# EVGP_Estop_Daugherboard.net
KiCad netlist of a schematic drawn in EAGLE
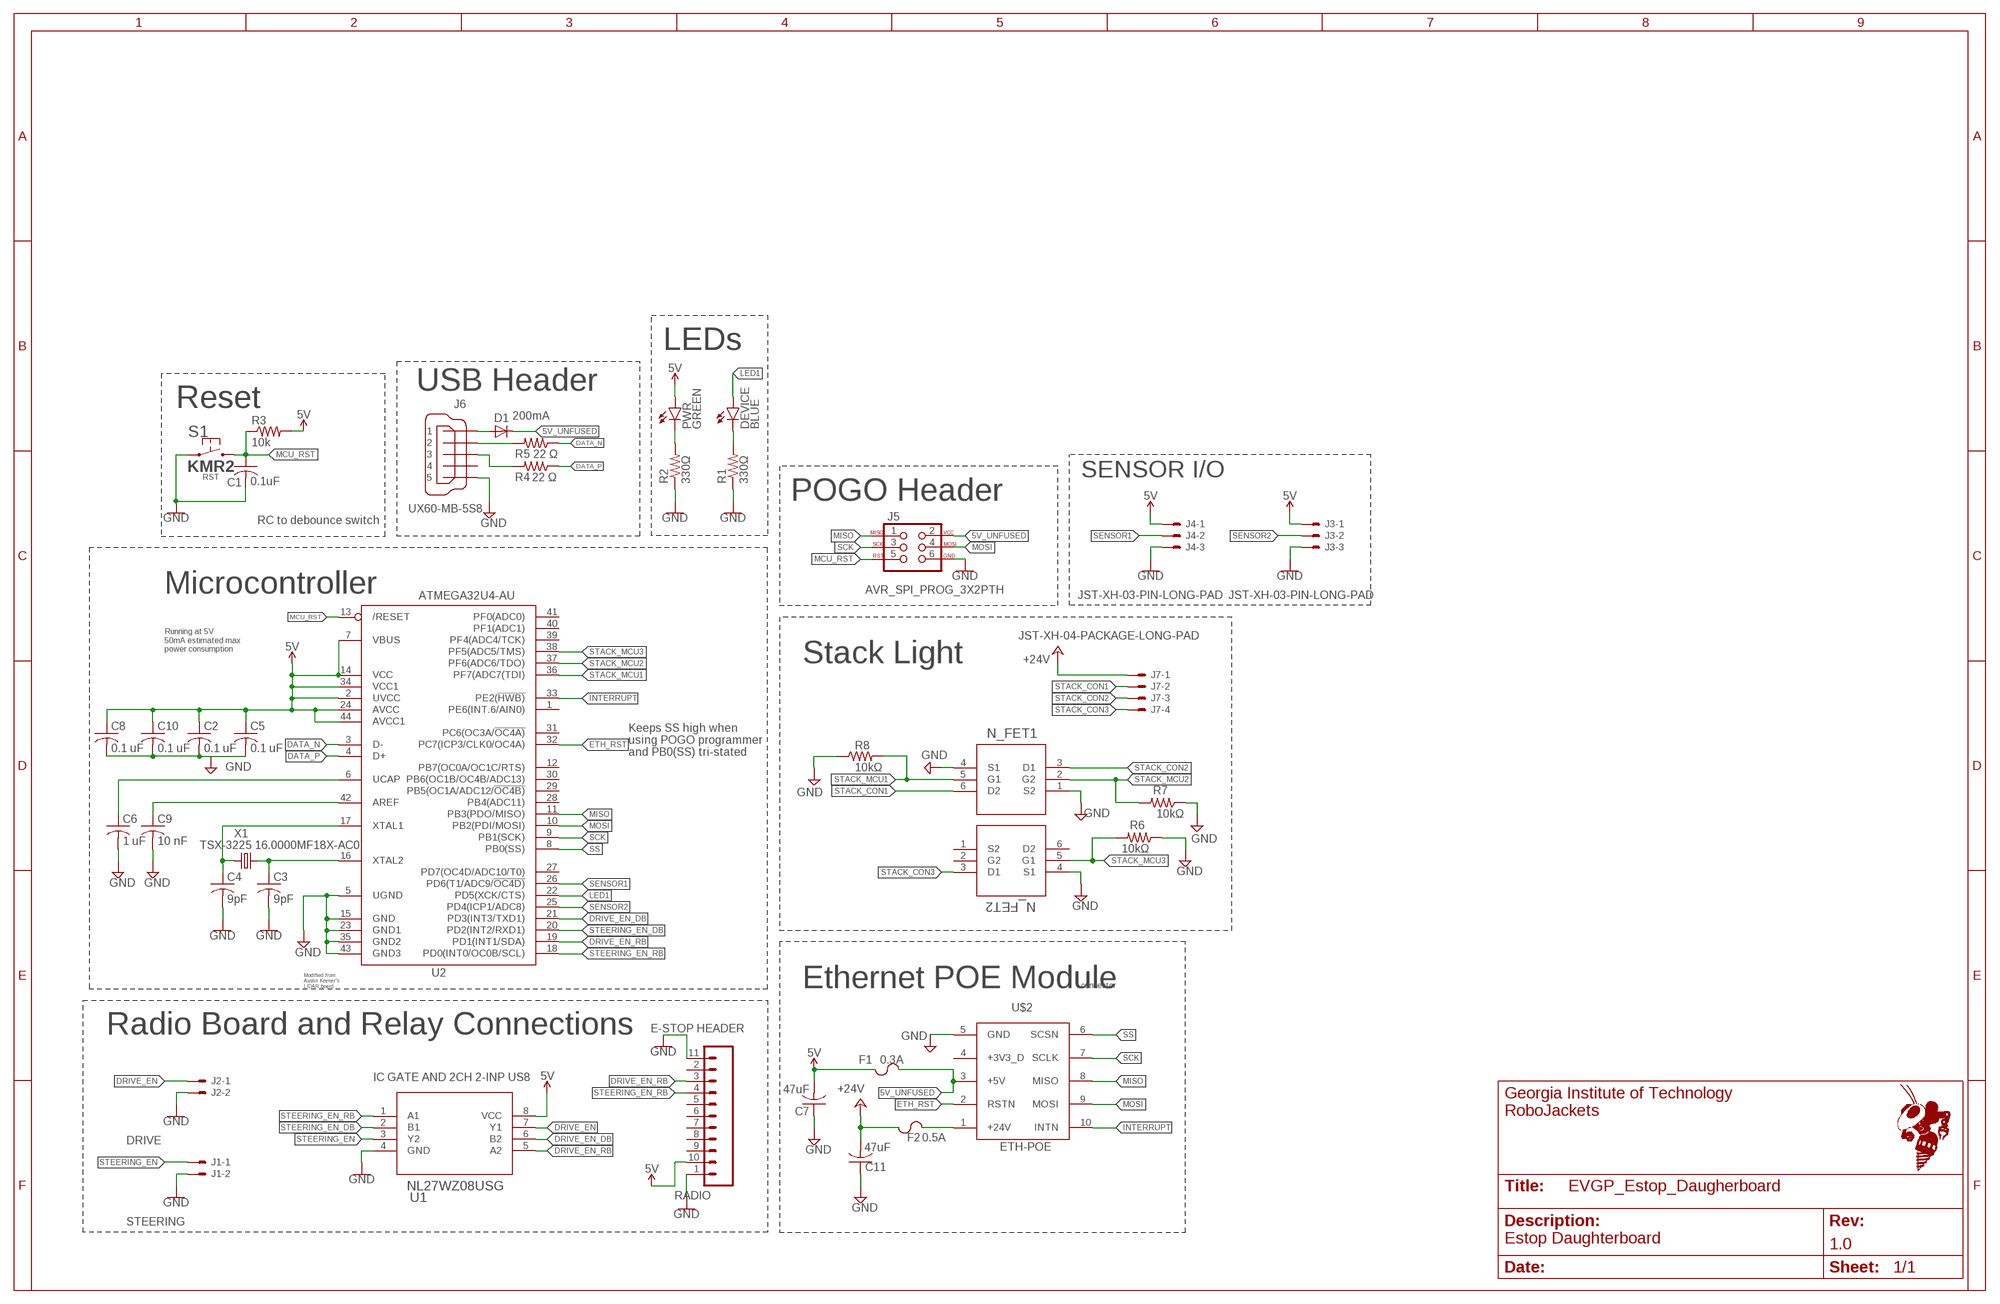
[diagram p0: schematic, sheet 1]

(export (version "E")
  (design (tool "Eeschema 10.0.6"))
  (components
    (comp (ref "C1")
      (value "0.1uF")
      (footprint "eagle-import:C0603")
      (libsource (lib "eagle-import") (part "C-USC0603"))
    )
    (comp (ref "C2")
      (value "0.1 uF")
      (footprint "eagle-import:C0603")
      (libsource (lib "eagle-import") (part "resistor_348_C-USC0603"))
    )
    (comp (ref "C3")
      (value "9pF")
      (footprint "eagle-import:C0603")
      (libsource (lib "eagle-import") (part "resistor_348_C-USC0603"))
    )
    (comp (ref "C4")
      (value "9pF")
      (footprint "eagle-import:C0603")
      (libsource (lib "eagle-import") (part "resistor_348_C-USC0603"))
    )
    (comp (ref "C5")
      (value "0.1 uF")
      (footprint "eagle-import:C0603")
      (libsource (lib "eagle-import") (part "resistor_348_C-USC0603"))
    )
    (comp (ref "C6")
      (value "1 uF")
      (footprint "eagle-import:C0603")
      (libsource (lib "eagle-import") (part "resistor_348_C-USC0603"))
    )
    (comp (ref "C7")
      (value "47uF")
      (footprint "eagle-import:C1206")
      (libsource (lib "eagle-import") (part "C-USC1206"))
    )
    (comp (ref "C8")
      (value "0.1 uF")
      (footprint "eagle-import:C0603")
      (libsource (lib "eagle-import") (part "resistor_348_C-USC0603"))
    )
    (comp (ref "C9")
      (value "10 nF")
      (footprint "eagle-import:C0603")
      (libsource (lib "eagle-import") (part "resistor_348_C-USC0603"))
    )
    (comp (ref "C10")
      (value "0.1 uF")
      (footprint "eagle-import:C0603")
      (libsource (lib "eagle-import") (part "resistor_348_C-USC0603"))
    )
    (comp (ref "C11")
      (value "47uF")
      (footprint "eagle-import:C1206")
      (libsource (lib "eagle-import") (part "C-USC1206"))
    )
    (comp (ref "D1")
      (value "200mA")
      (footprint "eagle-import:SOD323-R")
      (libsource (lib "eagle-import") (part "DIODE-SOD323-R"))
    )
    (comp (ref "DEVICE")
      (value "BLUE")
      (footprint "eagle-import:CHIP-LED0603")
      (libsource (lib "eagle-import") (part "LEDCHIP-LED0603"))
    )
    (comp (ref "F1")
      (value "0.3A")
      (footprint "eagle-import:F1206")
      (libsource (lib "eagle-import") (part "CHIP_FUSE1206"))
    )
    (comp (ref "F2")
      (value "0.5A")
      (footprint "eagle-import:F1206")
      (libsource (lib "eagle-import") (part "CHIP_FUSE1206"))
    )
    (comp (ref "J1")
      (value "STEERING")
      (footprint "eagle-import:JST-XH-02-PACKAGE-LONG-PAD")
      (libsource (lib "eagle-import") (part "JST-XH-02-PIN-LONG-PAD"))
    )
    (comp (ref "J2")
      (value "DRIVE")
      (footprint "eagle-import:JST-XH-02-PACKAGE-LONG-PAD")
      (libsource (lib "eagle-import") (part "JST-XH-02-PIN-LONG-PAD"))
    )
    (comp (ref "J3")
      (value "JST-XH-03-PIN-LONG-PAD")
      (footprint "eagle-import:JST-XH-03-PACKAGE-LONG-PAD")
      (libsource (lib "eagle-import") (part "JST-XH-03-PIN-LONG-PAD"))
    )
    (comp (ref "J4")
      (value "JST-XH-03-PIN-LONG-PAD")
      (footprint "eagle-import:JST-XH-03-PACKAGE-LONG-PAD")
      (libsource (lib "eagle-import") (part "JST-XH-03-PIN-LONG-PAD"))
    )
    (comp (ref "J5")
      (value "AVR_SPI_PROG_3X2PTH")
      (footprint "eagle-import:2X3")
      (libsource (lib "eagle-import") (part "AVR_SPI_PROG_3X2PTH"))
    )
    (comp (ref "J6")
      (value "UX60-MB-5S8")
      (footprint "eagle-import:UX60-MB-5S8")
      (libsource (lib "eagle-import") (part "UX60-MB-5S?8"))
    )
    (comp (ref "J7")
      (value "JST-XH-04-PACKAGE-LONG-PAD")
      (footprint "eagle-import:JST-XH-04-PACKAGE-LONG-PAD")
      (libsource (lib "eagle-import") (part "JST-XH-04-PIN-LONG-PAD"))
    )
    (comp (ref "PWR")
      (value "GREEN")
      (footprint "eagle-import:CHIP-LED0603")
      (libsource (lib "eagle-import") (part "LEDCHIP-LED0603"))
    )
    (comp (ref "Q1")
      (value "N_FET2")
      (footprint "eagle-import:SOT-363")
      (fields (field (name "MANUFACTURER_PART_NUMBER") "BSS84DW7F"))
      (libsource (lib "eagle-import") (part "BSS84DW-7-F"))
    )
    (comp (ref "Q2")
      (value "N_FET1")
      (footprint "eagle-import:SOT-363")
      (fields (field (name "MANUFACTURER_PART_NUMBER") "BSS84DW7F"))
      (libsource (lib "eagle-import") (part "BSS84DW-7-F"))
    )
    (comp (ref "R1")
      (value "330Ω")
      (footprint "eagle-import:R0603")
      (libsource (lib "eagle-import") (part "R-US_R0603"))
    )
    (comp (ref "R2")
      (value "330Ω")
      (footprint "eagle-import:R0603")
      (libsource (lib "eagle-import") (part "R-US_R0603"))
    )
    (comp (ref "R3")
      (value "10k")
      (footprint "eagle-import:R0603")
      (libsource (lib "eagle-import") (part "R-US_R0603"))
    )
    (comp (ref "R4")
      (value "22 Ω")
      (footprint "eagle-import:R0603")
      (libsource (lib "eagle-import") (part "R-US_R0603"))
    )
    (comp (ref "R5")
      (value "22 Ω")
      (footprint "eagle-import:R0603")
      (libsource (lib "eagle-import") (part "R-US_R0603"))
    )
    (comp (ref "R6")
      (value "10kΩ")
      (footprint "eagle-import:R0603")
      (libsource (lib "eagle-import") (part "R-US_R0603"))
    )
    (comp (ref "R7")
      (value "10kΩ")
      (footprint "eagle-import:R0603")
      (libsource (lib "eagle-import") (part "R-US_R0603"))
    )
    (comp (ref "R8")
      (value "10kΩ")
      (footprint "eagle-import:R0603")
      (libsource (lib "eagle-import") (part "R-US_R0603"))
    )
    (comp (ref "RADIO")
      (value "E-STOP HEADER")
      (footprint "eagle-import:RADIO_V1.3")
      (libsource (lib "eagle-import") (part "ESTOP_RADIO"))
    )
    (comp (ref "S1")
      (value "KMR2")
      (footprint "eagle-import:KMR2")
      (fields (field (name "FUNCTION") "Reset") (field (name "FUNCTION_1") "RST"))
      (libsource (lib "eagle-import") (part "KMR2"))
    )
    (comp (ref "U$2")
      (value "ETH-POE")
      (footprint "eagle-import:HDRVR10W64P4000X254_2X5_1016X508X254B")
      (libsource (lib "eagle-import") (part "ETH-POE"))
    )
    (comp (ref "U1")
      (value "NL27WZ08USG")
      (footprint "eagle-import:US8_2P40X2P10")
      (libsource (lib "eagle-import") (part "NL27WZ08USG"))
    )
    (comp (ref "U2")
      (value "ATMEGA32U4-AU")
      (footprint "eagle-import:TQFP44")
      (libsource (lib "eagle-import") (part "ATMEGA32U4-AU"))
    )
    (comp (ref "X1")
      (value "TSX-3225 16.0000MF18X-AC0")
      (footprint "eagle-import:XTAL-3.2X2.5")
      (libsource (lib "eagle-import") (part "XTAL-3.2X2.5"))
    )
  )
  (nets
    (net (code "1") (name "+24V") (class "Default")
      (node (ref "C11") (pin "2") (pinfunction "2_2") (pintype "passive"))
      (node (ref "F2") (pin "1") (pinfunction "1_1") (pintype "bidirectional"))
      (node (ref "J7") (pin "1") (pinfunction "S_1") (pintype "passive"))
    )
    (net (code "2") (name "5V") (class "Default")
      (node (ref "C10") (pin "1") (pinfunction "1_1") (pintype "passive"))
      (node (ref "C2") (pin "1") (pinfunction "1_1") (pintype "passive"))
      (node (ref "C5") (pin "1") (pinfunction "1_1") (pintype "passive"))
      (node (ref "C7") (pin "2") (pinfunction "2_2") (pintype "passive"))
      (node (ref "C8") (pin "1") (pinfunction "1_1") (pintype "passive"))
      (node (ref "F1") (pin "1") (pinfunction "1_1") (pintype "bidirectional"))
      (node (ref "J3") (pin "1") (pinfunction "S_1") (pintype "passive"))
      (node (ref "J4") (pin "1") (pinfunction "S_1") (pintype "passive"))
      (node (ref "PWR") (pin "A") (pinfunction "A_A") (pintype "passive"))
      (node (ref "R3") (pin "2") (pinfunction "2_2") (pintype "passive"))
      (node (ref "RADIO") (pin "10") (pinfunction "5V_10") (pintype "passive"))
      (node (ref "U1") (pin "8") (pinfunction "VCC_8") (pintype "power_in"))
      (node (ref "U2") (pin "14") (pinfunction "VCC_14") (pintype "bidirectional"))
      (node (ref "U2") (pin "2") (pinfunction "UVCC_2") (pintype "bidirectional"))
      (node (ref "U2") (pin "24") (pinfunction "AVCC_24") (pintype "bidirectional"))
      (node (ref "U2") (pin "34") (pinfunction "VCC1_34") (pintype "bidirectional"))
      (node (ref "U2") (pin "44") (pinfunction "AVCC1_44") (pintype "bidirectional"))
      (node (ref "U2") (pin "7") (pinfunction "VBUS_7") (pintype "bidirectional"))
    )
    (net (code "3") (name "5V_UNFUSED") (class "Default")
      (node (ref "D1") (pin "C") (pinfunction "C_C") (pintype "passive"))
      (node (ref "F1") (pin "2") (pinfunction "2_2") (pintype "bidirectional"))
      (node (ref "J5") (pin "2") (pinfunction "2_2") (pintype "passive"))
      (node (ref "U$2") (pin "3") (pinfunction "+5V_3") (pintype "bidirectional"))
    )
    (net (code "4") (name "DATA_N") (class "Default")
      (node (ref "R5") (pin "1") (pinfunction "1_1") (pintype "passive"))
      (node (ref "U2") (pin "3") (pinfunction "D-_3") (pintype "bidirectional"))
    )
    (net (code "5") (name "DATA_P") (class "Default")
      (node (ref "R4") (pin "1") (pinfunction "1_1") (pintype "passive"))
      (node (ref "U2") (pin "4") (pinfunction "D+_4") (pintype "bidirectional"))
    )
    (net (code "6") (name "DRIVE_EN") (class "Default")
      (node (ref "J2") (pin "1") (pinfunction "S_1") (pintype "passive"))
      (node (ref "U1") (pin "7") (pinfunction "Y1_7") (pintype "output"))
    )
    (net (code "7") (name "DRIVE_EN_DB") (class "Default")
      (node (ref "U1") (pin "6") (pinfunction "B2_6") (pintype "input"))
      (node (ref "U2") (pin "21") (pinfunction "PD3(INT3/TXD1)_21") (pintype "bidirectional"))
    )
    (net (code "8") (name "DRIVE_EN_RB") (class "Default")
      (node (ref "RADIO") (pin "3") (pinfunction "D1_3") (pintype "passive"))
      (node (ref "U1") (pin "5") (pinfunction "A2_5") (pintype "input"))
      (node (ref "U2") (pin "19") (pinfunction "PD1(INT1/SDA)_19") (pintype "bidirectional"))
    )
    (net (code "9") (name "ETH_RST") (class "Default")
      (node (ref "U$2") (pin "2") (pinfunction "RSTN_2") (pintype "bidirectional"))
      (node (ref "U2") (pin "32") (pinfunction "PC7(ICP3/CLK0/OC4A)_32") (pintype "bidirectional"))
    )
    (net (code "10") (name "GND") (class "Default")
      (node (ref "C1") (pin "2") (pinfunction "2_2") (pintype "passive"))
      (node (ref "C10") (pin "2") (pinfunction "2_2") (pintype "passive"))
      (node (ref "C11") (pin "1") (pinfunction "1_1") (pintype "passive"))
      (node (ref "C2") (pin "2") (pinfunction "2_2") (pintype "passive"))
      (node (ref "C3") (pin "2") (pinfunction "2_2") (pintype "passive"))
      (node (ref "C4") (pin "2") (pinfunction "2_2") (pintype "passive"))
      (node (ref "C5") (pin "2") (pinfunction "2_2") (pintype "passive"))
      (node (ref "C6") (pin "2") (pinfunction "2_2") (pintype "passive"))
      (node (ref "C7") (pin "1") (pinfunction "1_1") (pintype "passive"))
      (node (ref "C8") (pin "2") (pinfunction "2_2") (pintype "passive"))
      (node (ref "C9") (pin "2") (pinfunction "2_2") (pintype "passive"))
      (node (ref "J1") (pin "2") (pinfunction "S_2") (pintype "passive"))
      (node (ref "J2") (pin "2") (pinfunction "S_2") (pintype "passive"))
      (node (ref "J3") (pin "3") (pinfunction "S_3") (pintype "passive"))
      (node (ref "J4") (pin "3") (pinfunction "S_3") (pintype "passive"))
      (node (ref "J5") (pin "6") (pinfunction "6_6") (pintype "passive"))
      (node (ref "J6") (pin "5") (pinfunction "5_5") (pintype "passive"))
      (node (ref "Q1") (pin "4") (pinfunction "S1_4") (pintype "passive"))
      (node (ref "Q2") (pin "1") (pinfunction "S2_1") (pintype "passive"))
      (node (ref "Q2") (pin "4") (pinfunction "S1_4") (pintype "passive"))
      (node (ref "R1") (pin "1") (pinfunction "1_1") (pintype "passive"))
      (node (ref "R2") (pin "1") (pinfunction "1_1") (pintype "passive"))
      (node (ref "R6") (pin "1") (pinfunction "1_1") (pintype "passive"))
      (node (ref "R7") (pin "1") (pinfunction "1_1") (pintype "passive"))
      (node (ref "R8") (pin "1") (pinfunction "1_1") (pintype "passive"))
      (node (ref "RADIO") (pin "1") (pinfunction "GND_1") (pintype "passive"))
      (node (ref "RADIO") (pin "11") (pinfunction "GND_11") (pintype "passive"))
      (node (ref "S1") (pin "1.1") (pinfunction "1_1.1") (pintype "passive"))
      (node (ref "S1") (pin "1.2") (pinfunction "1_1.2") (pintype "passive"))
      (node (ref "U$2") (pin "5") (pinfunction "GND_5") (pintype "bidirectional"))
      (node (ref "U1") (pin "4") (pinfunction "GND_4") (pintype "power_in"))
      (node (ref "U2") (pin "15") (pinfunction "GND_15") (pintype "bidirectional"))
      (node (ref "U2") (pin "23") (pinfunction "GND1_23") (pintype "bidirectional"))
      (node (ref "U2") (pin "35") (pinfunction "GND2_35") (pintype "bidirectional"))
      (node (ref "U2") (pin "43") (pinfunction "GND3_43") (pintype "bidirectional"))
      (node (ref "U2") (pin "5") (pinfunction "UGND_5") (pintype "bidirectional"))
    )
    (net (code "11") (name "INTERRUPT") (class "Default")
      (node (ref "U$2") (pin "10") (pinfunction "INTN_10") (pintype "bidirectional"))
      (node (ref "U2") (pin "33") (pinfunction "PE2(~{HWB})_33") (pintype "bidirectional"))
    )
    (net (code "12") (name "LED1") (class "Default")
      (node (ref "DEVICE") (pin "A") (pinfunction "A_A") (pintype "passive"))
      (node (ref "U2") (pin "22") (pinfunction "PD5(XCK/CTS)_22") (pintype "bidirectional"))
    )
    (net (code "13") (name "MCU_RST") (class "Default")
      (node (ref "C1") (pin "1") (pinfunction "1_1") (pintype "passive"))
      (node (ref "J5") (pin "5") (pinfunction "5_5") (pintype "passive"))
      (node (ref "R3") (pin "1") (pinfunction "1_1") (pintype "passive"))
      (node (ref "S1") (pin "2.1") (pinfunction "2_2.1") (pintype "passive"))
      (node (ref "S1") (pin "2.2") (pinfunction "2_2.2") (pintype "passive"))
      (node (ref "U2") (pin "13") (pinfunction "/RESET_13") (pintype "bidirectional"))
    )
    (net (code "14") (name "MISO") (class "Default")
      (node (ref "J5") (pin "1") (pinfunction "1_1") (pintype "passive"))
      (node (ref "U$2") (pin "8") (pinfunction "MISO_8") (pintype "bidirectional"))
      (node (ref "U2") (pin "11") (pinfunction "PB3(PDO/MISO)_11") (pintype "bidirectional"))
    )
    (net (code "15") (name "MOSI") (class "Default")
      (node (ref "J5") (pin "4") (pinfunction "4_4") (pintype "passive"))
      (node (ref "U$2") (pin "9") (pinfunction "MOSI_9") (pintype "bidirectional"))
      (node (ref "U2") (pin "10") (pinfunction "PB2(PDI/MOSI)_10") (pintype "bidirectional"))
    )
    (net (code "16") (name "Net-(D1-PadA)") (class "Default")
      (node (ref "D1") (pin "A") (pinfunction "A_A") (pintype "passive"))
      (node (ref "J6") (pin "1") (pinfunction "1_1") (pintype "passive"))
    )
    (net (code "17") (name "Net-(DEVICE-PadC)") (class "Default")
      (node (ref "DEVICE") (pin "C") (pinfunction "C_C") (pintype "passive"))
      (node (ref "R1") (pin "2") (pinfunction "2_2") (pintype "passive"))
    )
    (net (code "18") (name "Net-(J6-Pad2)") (class "Default")
      (node (ref "J6") (pin "2") (pinfunction "2_2") (pintype "passive"))
      (node (ref "R5") (pin "2") (pinfunction "2_2") (pintype "passive"))
    )
    (net (code "19") (name "Net-(J6-Pad3)") (class "Default")
      (node (ref "J6") (pin "3") (pinfunction "3_3") (pintype "passive"))
      (node (ref "R4") (pin "2") (pinfunction "2_2") (pintype "passive"))
    )
    (net (code "20") (name "Net-(PWR-PadC)") (class "Default")
      (node (ref "PWR") (pin "C") (pinfunction "C_C") (pintype "passive"))
      (node (ref "R2") (pin "2") (pinfunction "2_2") (pintype "passive"))
    )
    (net (code "21") (name "Net-(U$2-+24V)") (class "Default")
      (node (ref "F2") (pin "2") (pinfunction "2_2") (pintype "bidirectional"))
      (node (ref "U$2") (pin "1") (pinfunction "+24V_1") (pintype "bidirectional"))
    )
    (net (code "22") (name "Net-(U2-AREF)") (class "Default")
      (node (ref "C9") (pin "1") (pinfunction "1_1") (pintype "passive"))
      (node (ref "U2") (pin "42") (pinfunction "AREF_42") (pintype "bidirectional"))
    )
    (net (code "23") (name "Net-(U2-UCAP)") (class "Default")
      (node (ref "C6") (pin "1") (pinfunction "1_1") (pintype "passive"))
      (node (ref "U2") (pin "6") (pinfunction "UCAP_6") (pintype "bidirectional"))
    )
    (net (code "24") (name "Net-(U2-XTAL1)") (class "Default")
      (node (ref "C4") (pin "1") (pinfunction "1_1") (pintype "passive"))
      (node (ref "U2") (pin "17") (pinfunction "XTAL1_17") (pintype "bidirectional"))
      (node (ref "X1") (pin "1") (pinfunction "1_1") (pintype "passive"))
    )
    (net (code "25") (name "Net-(U2-XTAL2)") (class "Default")
      (node (ref "C3") (pin "1") (pinfunction "1_1") (pintype "passive"))
      (node (ref "U2") (pin "16") (pinfunction "XTAL2_16") (pintype "bidirectional"))
      (node (ref "X1") (pin "3") (pinfunction "2_3") (pintype "passive"))
    )
    (net (code "26") (name "SCK") (class "Default")
      (node (ref "J5") (pin "3") (pinfunction "3_3") (pintype "passive"))
      (node (ref "U$2") (pin "7") (pinfunction "SCLK_7") (pintype "bidirectional"))
      (node (ref "U2") (pin "9") (pinfunction "PB1(SCK)_9") (pintype "bidirectional"))
    )
    (net (code "27") (name "SENSOR1") (class "Default")
      (node (ref "J4") (pin "2") (pinfunction "S_2") (pintype "passive"))
      (node (ref "U2") (pin "26") (pinfunction "PD6(T1/ADC9/~{OC4D})_26") (pintype "bidirectional"))
    )
    (net (code "28") (name "SENSOR2") (class "Default")
      (node (ref "J3") (pin "2") (pinfunction "S_2") (pintype "passive"))
      (node (ref "U2") (pin "25") (pinfunction "PD4(ICP1/ADC8)_25") (pintype "bidirectional"))
    )
    (net (code "29") (name "SS") (class "Default")
      (node (ref "U$2") (pin "6") (pinfunction "SCSN_6") (pintype "bidirectional"))
      (node (ref "U2") (pin "8") (pinfunction "PB0(SS)_8") (pintype "bidirectional"))
    )
    (net (code "30") (name "STACK_CON1") (class "Default")
      (node (ref "J7") (pin "2") (pinfunction "S_2") (pintype "passive"))
      (node (ref "Q2") (pin "6") (pinfunction "D2_6") (pintype "passive"))
    )
    (net (code "31") (name "STACK_CON2") (class "Default")
      (node (ref "J7") (pin "3") (pinfunction "S_3") (pintype "passive"))
      (node (ref "Q2") (pin "3") (pinfunction "D1_3") (pintype "passive"))
    )
    (net (code "32") (name "STACK_CON3") (class "Default")
      (node (ref "J7") (pin "4") (pinfunction "S_4") (pintype "passive"))
      (node (ref "Q1") (pin "3") (pinfunction "D1_3") (pintype "passive"))
    )
    (net (code "33") (name "STACK_MCU1") (class "Default")
      (node (ref "Q2") (pin "5") (pinfunction "G1_5") (pintype "passive"))
      (node (ref "R8") (pin "2") (pinfunction "2_2") (pintype "passive"))
      (node (ref "U2") (pin "36") (pinfunction "PF7(ADC7(TDI)_36") (pintype "bidirectional"))
    )
    (net (code "34") (name "STACK_MCU2") (class "Default")
      (node (ref "Q2") (pin "2") (pinfunction "G2_2") (pintype "passive"))
      (node (ref "R7") (pin "2") (pinfunction "2_2") (pintype "passive"))
      (node (ref "U2") (pin "37") (pinfunction "PF6(ADC6/TDO)_37") (pintype "bidirectional"))
    )
    (net (code "35") (name "STACK_MCU3") (class "Default")
      (node (ref "Q1") (pin "5") (pinfunction "G1_5") (pintype "passive"))
      (node (ref "R6") (pin "2") (pinfunction "2_2") (pintype "passive"))
      (node (ref "U2") (pin "38") (pinfunction "PF5(ADC5/TMS)_38") (pintype "bidirectional"))
    )
    (net (code "36") (name "STEERING_EN") (class "Default")
      (node (ref "J1") (pin "1") (pinfunction "S_1") (pintype "passive"))
      (node (ref "U1") (pin "3") (pinfunction "Y2_3") (pintype "output"))
    )
    (net (code "37") (name "STEERING_EN_DB") (class "Default")
      (node (ref "U1") (pin "2") (pinfunction "B1_2") (pintype "input"))
      (node (ref "U2") (pin "20") (pinfunction "PD2(INT2/RXD1)_20") (pintype "bidirectional"))
    )
    (net (code "38") (name "STEERING_EN_RB") (class "Default")
      (node (ref "RADIO") (pin "4") (pinfunction "D2_4") (pintype "passive"))
      (node (ref "U1") (pin "1") (pinfunction "A1_1") (pintype "input"))
      (node (ref "U2") (pin "18") (pinfunction "PD0(INT0/OC0B/SCL)_18") (pintype "bidirectional"))
    )
    (net (code "39") (name "unconnected-(J6-Pad4)") (class "Default")
      (node (ref "J6") (pin "4") (pinfunction "4_4") (pintype "passive"))
    )
    (net (code "40") (name "unconnected-(Q1-D2-Pad6)") (class "Default")
      (node (ref "Q1") (pin "6") (pinfunction "D2_6") (pintype "passive"))
    )
    (net (code "41") (name "unconnected-(Q1-G2-Pad2)") (class "Default")
      (node (ref "Q1") (pin "2") (pinfunction "G2_2") (pintype "passive"))
    )
    (net (code "42") (name "unconnected-(Q1-S2-Pad1)") (class "Default")
      (node (ref "Q1") (pin "1") (pinfunction "S2_1") (pintype "passive"))
    )
    (net (code "43") (name "unconnected-(RADIO-D3-Pad5)") (class "Default")
      (node (ref "RADIO") (pin "5") (pinfunction "D3_5") (pintype "passive"))
    )
    (net (code "44") (name "unconnected-(RADIO-D4-Pad6)") (class "Default")
      (node (ref "RADIO") (pin "6") (pinfunction "D4_6") (pintype "passive"))
    )
    (net (code "45") (name "unconnected-(RADIO-D5-Pad7)") (class "Default")
      (node (ref "RADIO") (pin "7") (pinfunction "D5_7") (pintype "passive"))
    )
    (net (code "46") (name "unconnected-(RADIO-D6-Pad8)") (class "Default")
      (node (ref "RADIO") (pin "8") (pinfunction "D6_8") (pintype "passive"))
    )
    (net (code "47") (name "unconnected-(RADIO-D7-Pad9)") (class "Default")
      (node (ref "RADIO") (pin "9") (pinfunction "D7_9") (pintype "passive"))
    )
    (net (code "48") (name "unconnected-(RADIO-RST-Pad2)") (class "Default")
      (node (ref "RADIO") (pin "2") (pinfunction "RST_2") (pintype "passive"))
    )
    (net (code "49") (name "unconnected-(U$2-+3V3_D-Pad4)") (class "Default")
      (node (ref "U$2") (pin "4") (pinfunction "+3V3_D_4") (pintype "bidirectional"))
    )
    (net (code "50") (name "unconnected-(U2-PB4(ADC11)-Pad28)") (class "Default")
      (node (ref "U2") (pin "28") (pinfunction "PB4(ADC11)_28") (pintype "bidirectional"))
    )
    (net (code "51") (name "unconnected-(U2-PB5(OC1A{slash}ADC12{slash}~{OC4B})-Pad29)") (class "Default")
      (node (ref "U2") (pin "29") (pinfunction "PB5(OC1A/ADC12/~{OC4B})_29") (pintype "bidirectional"))
    )
    (net (code "52") (name "unconnected-(U2-PB6(OC1B{slash}OC4B{slash}ADC13)-Pad30)") (class "Default")
      (node (ref "U2") (pin "30") (pinfunction "PB6(OC1B/OC4B/ADC13)_30") (pintype "bidirectional"))
    )
    (net (code "53") (name "unconnected-(U2-PB7(OC0A{slash}OC1C{slash}RTS)-Pad12)") (class "Default")
      (node (ref "U2") (pin "12") (pinfunction "PB7(OC0A/OC1C/RTS)_12") (pintype "bidirectional"))
    )
    (net (code "54") (name "unconnected-(U2-PC6(OC3A{slash}~{OC4A})-Pad31)") (class "Default")
      (node (ref "U2") (pin "31") (pinfunction "PC6(OC3A/~{OC4A})_31") (pintype "bidirectional"))
    )
    (net (code "55") (name "unconnected-(U2-PD7(OC4D{slash}ADC10{slash}T0)-Pad27)") (class "Default")
      (node (ref "U2") (pin "27") (pinfunction "PD7(OC4D/ADC10/T0)_27") (pintype "bidirectional"))
    )
    (net (code "56") (name "unconnected-(U2-PE6(INT.6{slash}AIN0)-Pad1)") (class "Default")
      (node (ref "U2") (pin "1") (pinfunction "PE6(INT.6/AIN0)_1") (pintype "bidirectional"))
    )
    (net (code "57") (name "unconnected-(U2-PF0(ADC0)-Pad41)") (class "Default")
      (node (ref "U2") (pin "41") (pinfunction "PF0(ADC0)_41") (pintype "bidirectional"))
    )
    (net (code "58") (name "unconnected-(U2-PF1(ADC1)-Pad40)") (class "Default")
      (node (ref "U2") (pin "40") (pinfunction "PF1(ADC1)_40") (pintype "bidirectional"))
    )
    (net (code "59") (name "unconnected-(U2-PF4(ADC4{slash}TCK)-Pad39)") (class "Default")
      (node (ref "U2") (pin "39") (pinfunction "PF4(ADC4/TCK)_39") (pintype "bidirectional"))
    )
  )
)
